# nes-forever.net
KiCad netlist of a schematic drawn in EAGLE
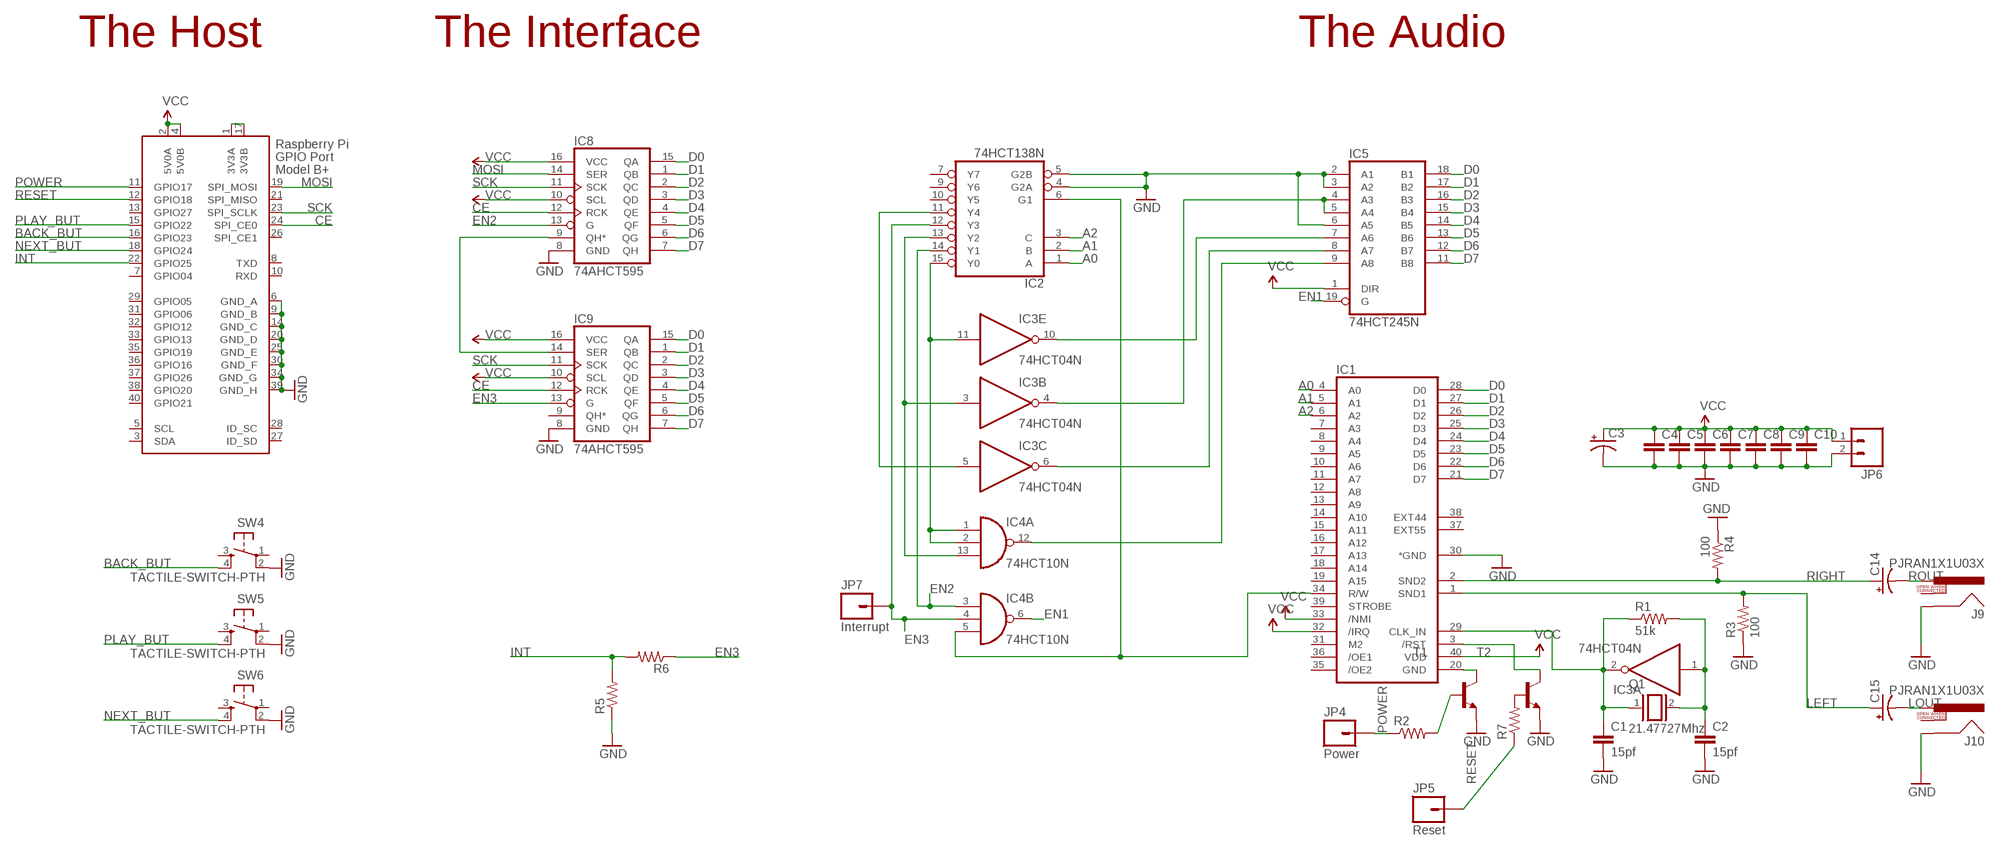
[diagram p0: schematic, sheet 1]

(export (version "E")
  (design (tool "Eeschema 10.0.6"))
  (components
    (comp (ref "C1")
      (value "15pf")
      (footprint "eagle-import:C025-024X044")
      (libsource (lib "eagle-import") (part "C-EU025-024X044"))
    )
    (comp (ref "C2")
      (value "15pf")
      (footprint "eagle-import:C025-024X044")
      (libsource (lib "eagle-import") (part "C-EU025-024X044"))
    )
    (comp (ref "C3")
      (value "CPOL-USE5-8.5")
      (footprint "eagle-import:E5-8,5")
      (libsource (lib "eagle-import") (part "CPOL-USE5-8.5"))
    )
    (comp (ref "C4")
      (value "C-EU025-024X044")
      (footprint "eagle-import:C025-024X044")
      (libsource (lib "eagle-import") (part "C-EU025-024X044"))
    )
    (comp (ref "C5")
      (value "C-EU025-024X044")
      (footprint "eagle-import:C025-024X044")
      (libsource (lib "eagle-import") (part "C-EU025-024X044"))
    )
    (comp (ref "C6")
      (value "C-EU025-024X044")
      (footprint "eagle-import:C025-024X044")
      (libsource (lib "eagle-import") (part "C-EU025-024X044"))
    )
    (comp (ref "C7")
      (value "C-EU025-024X044")
      (footprint "eagle-import:C025-024X044")
      (libsource (lib "eagle-import") (part "C-EU025-024X044"))
    )
    (comp (ref "C8")
      (value "C-EU025-024X044")
      (footprint "eagle-import:C025-024X044")
      (libsource (lib "eagle-import") (part "C-EU025-024X044"))
    )
    (comp (ref "C9")
      (value "C-EU025-024X044")
      (footprint "eagle-import:C025-024X044")
      (libsource (lib "eagle-import") (part "C-EU025-024X044"))
    )
    (comp (ref "C10")
      (value "C-EU025-024X044")
      (footprint "eagle-import:C025-024X044")
      (libsource (lib "eagle-import") (part "C-EU025-024X044"))
    )
    (comp (ref "C14")
      (value "CPOL-USE2-4")
      (footprint "eagle-import:E2-4")
      (libsource (lib "eagle-import") (part "resistor_CPOL-USE2-4"))
    )
    (comp (ref "C15")
      (value "CPOL-USE2-4")
      (footprint "eagle-import:E2-4")
      (libsource (lib "eagle-import") (part "resistor_CPOL-USE2-4"))
    )
    (comp (ref "IC1")
      (value "2A03")
      (footprint "eagle-import:DIL40")
      (libsource (lib "eagle-import") (part "2A03"))
    )
    (comp (ref "IC2")
      (value "74HCT138N")
      (footprint "eagle-import:DIL16")
      (libsource (lib "eagle-import") (part "74138NHCT"))
    )
    (comp (ref "IC3")
      (value "74HCT04N")
      (footprint "eagle-import:DIL14")
      (libsource (lib "eagle-import") (part "7404NHCT"))
    )
    (comp (ref "IC4")
      (value "74HCT10N")
      (footprint "eagle-import:DIL14")
      (libsource (lib "eagle-import") (part "7410NHCT"))
    )
    (comp (ref "IC5")
      (value "74HCT245N")
      (footprint "eagle-import:DIL20")
      (libsource (lib "eagle-import") (part "74245NHCT"))
    )
    (comp (ref "IC8")
      (value "74AHCT595")
      (footprint "eagle-import:DIL16")
      (libsource (lib "eagle-import") (part "74595NLS"))
    )
    (comp (ref "IC9")
      (value "74AHCT595")
      (footprint "eagle-import:DIL16")
      (libsource (lib "eagle-import") (part "74595NLS"))
    )
    (comp (ref "J9")
      (value "PJRAN1X1U03X")
      (footprint "eagle-import:RCA")
      (libsource (lib "eagle-import") (part "RCA"))
    )
    (comp (ref "J10")
      (value "PJRAN1X1U03X")
      (footprint "eagle-import:RCA")
      (libsource (lib "eagle-import") (part "RCA"))
    )
    (comp (ref "JP4")
      (value "Power")
      (footprint "eagle-import:1X01")
      (libsource (lib "eagle-import") (part "M01PTH"))
    )
    (comp (ref "JP5")
      (value "Reset")
      (footprint "eagle-import:1X01")
      (libsource (lib "eagle-import") (part "M01PTH"))
    )
    (comp (ref "JP6")
      (value "M02")
      (footprint "eagle-import:1X02_LONGPADS")
      (libsource (lib "eagle-import") (part "M02"))
    )
    (comp (ref "JP7")
      (value "Interrupt")
      (footprint "eagle-import:1X01")
      (libsource (lib "eagle-import") (part "M01PTH"))
    )
    (comp (ref "Q1")
      (value "21.47727Mhz")
      (footprint "eagle-import:Q")
      (libsource (lib "eagle-import") (part "XTAL"))
    )
    (comp (ref "R1")
      (value "51k")
      (footprint "eagle-import:0207_7")
      (libsource (lib "eagle-import") (part "R-US_0207/7"))
    )
    (comp (ref "R2")
      (value "R-US_0207/7")
      (footprint "eagle-import:0207_7")
      (libsource (lib "eagle-import") (part "R-US_0207/7"))
    )
    (comp (ref "R3")
      (value "100")
      (footprint "eagle-import:0207_7")
      (libsource (lib "eagle-import") (part "R-US_0207/7"))
    )
    (comp (ref "R4")
      (value "100")
      (footprint "eagle-import:0207_7")
      (libsource (lib "eagle-import") (part "R-US_0207/7"))
    )
    (comp (ref "R5")
      (value "R-US_0207/7")
      (footprint "eagle-import:0207_7")
      (libsource (lib "eagle-import") (part "R-US_0207/7"))
    )
    (comp (ref "R6")
      (value "R-US_0207/7")
      (footprint "eagle-import:0207_7")
      (libsource (lib "eagle-import") (part "R-US_0207/7"))
    )
    (comp (ref "R7")
      (value "R-US_0207/7")
      (footprint "eagle-import:0207_7")
      (libsource (lib "eagle-import") (part "R-US_0207/7"))
    )
    (comp (ref "SW4")
      (value "TACTILE-SWITCH-PTH")
      (footprint "eagle-import:TAC-SWITCH-PTH")
      (libsource (lib "eagle-import") (part "TACTILE-SWITCH-PTH"))
    )
    (comp (ref "SW5")
      (value "TACTILE-SWITCH-PTH")
      (footprint "eagle-import:TAC-SWITCH-PTH")
      (libsource (lib "eagle-import") (part "TACTILE-SWITCH-PTH"))
    )
    (comp (ref "SW6")
      (value "TACTILE-SWITCH-PTH")
      (footprint "eagle-import:TAC-SWITCH-PTH")
      (libsource (lib "eagle-import") (part "TACTILE-SWITCH-PTH"))
    )
    (comp (ref "T1")
      (value "2N2222-NPN-TO92-EBC")
      (footprint "eagle-import:TO92-EBC")
      (libsource (lib "eagle-import") (part "-NPN-TO92-EBC2N2222"))
    )
    (comp (ref "T2")
      (value "2N2222-NPN-TO92-EBC")
      (footprint "eagle-import:TO92-EBC")
      (libsource (lib "eagle-import") (part "-NPN-TO92-EBC2N2222"))
    )
    (comp (ref "X2")
      (value "RASPI_BOARD_B+#_E4")
      (footprint "eagle-import:RASPI_BOARD_B+_EDGES_4DRILL")
      (libsource (lib "eagle-import") (part "RASPI_BOARD_B+#_E4"))
    )
  )
  (nets
    (net (code "1") (name "/A0") (class "Default")
      (node (ref "IC1") (pin "4") (pinfunction "A0_4") (pintype "output"))
      (node (ref "IC2") (pin "1") (pinfunction "A_1") (pintype "input"))
    )
    (net (code "2") (name "/A1") (class "Default")
      (node (ref "IC1") (pin "5") (pinfunction "A1_5") (pintype "output"))
      (node (ref "IC2") (pin "2") (pinfunction "B_2") (pintype "input"))
    )
    (net (code "3") (name "/A2") (class "Default")
      (node (ref "IC1") (pin "6") (pinfunction "A2_6") (pintype "output"))
      (node (ref "IC2") (pin "3") (pinfunction "C_3") (pintype "input"))
    )
    (net (code "4") (name "/BACK_BUT") (class "Default")
      (node (ref "SW4") (pin "4") (pinfunction "4_4") (pintype "passive"))
      (node (ref "X2") (pin "16") (pinfunction "GPIO23_16") (pintype "bidirectional"))
    )
    (net (code "5") (name "/CE") (class "Default")
      (node (ref "IC8") (pin "12") (pinfunction "RCK_12") (pintype "input"))
      (node (ref "IC9") (pin "12") (pinfunction "RCK_12") (pintype "input"))
      (node (ref "X2") (pin "24") (pinfunction "SPI_CE0_24") (pintype "bidirectional"))
    )
    (net (code "6") (name "/D0") (class "Default")
      (node (ref "IC1") (pin "28") (pinfunction "D0_28") (pintype "bidirectional"))
      (node (ref "IC5") (pin "18") (pinfunction "B1_18") (pintype "bidirectional"))
      (node (ref "IC8") (pin "15") (pinfunction "QA_15") (pintype "tri_state"))
      (node (ref "IC9") (pin "15") (pinfunction "QA_15") (pintype "tri_state"))
    )
    (net (code "7") (name "/D1") (class "Default")
      (node (ref "IC1") (pin "27") (pinfunction "D1_27") (pintype "bidirectional"))
      (node (ref "IC5") (pin "17") (pinfunction "B2_17") (pintype "bidirectional"))
      (node (ref "IC8") (pin "1") (pinfunction "QB_1") (pintype "tri_state"))
      (node (ref "IC9") (pin "1") (pinfunction "QB_1") (pintype "tri_state"))
    )
    (net (code "8") (name "/D2") (class "Default")
      (node (ref "IC1") (pin "26") (pinfunction "D2_26") (pintype "bidirectional"))
      (node (ref "IC5") (pin "16") (pinfunction "B3_16") (pintype "bidirectional"))
      (node (ref "IC8") (pin "2") (pinfunction "QC_2") (pintype "tri_state"))
      (node (ref "IC9") (pin "2") (pinfunction "QC_2") (pintype "tri_state"))
    )
    (net (code "9") (name "/D3") (class "Default")
      (node (ref "IC1") (pin "25") (pinfunction "D3_25") (pintype "bidirectional"))
      (node (ref "IC5") (pin "15") (pinfunction "B4_15") (pintype "bidirectional"))
      (node (ref "IC8") (pin "3") (pinfunction "QD_3") (pintype "tri_state"))
      (node (ref "IC9") (pin "3") (pinfunction "QD_3") (pintype "tri_state"))
    )
    (net (code "10") (name "/D4") (class "Default")
      (node (ref "IC1") (pin "24") (pinfunction "D4_24") (pintype "bidirectional"))
      (node (ref "IC5") (pin "14") (pinfunction "B5_14") (pintype "bidirectional"))
      (node (ref "IC8") (pin "4") (pinfunction "QE_4") (pintype "tri_state"))
      (node (ref "IC9") (pin "4") (pinfunction "QE_4") (pintype "tri_state"))
    )
    (net (code "11") (name "/D5") (class "Default")
      (node (ref "IC1") (pin "23") (pinfunction "D5_23") (pintype "bidirectional"))
      (node (ref "IC5") (pin "13") (pinfunction "B6_13") (pintype "bidirectional"))
      (node (ref "IC8") (pin "5") (pinfunction "QF_5") (pintype "tri_state"))
      (node (ref "IC9") (pin "5") (pinfunction "QF_5") (pintype "tri_state"))
    )
    (net (code "12") (name "/D6") (class "Default")
      (node (ref "IC1") (pin "22") (pinfunction "D6_22") (pintype "bidirectional"))
      (node (ref "IC5") (pin "12") (pinfunction "B7_12") (pintype "bidirectional"))
      (node (ref "IC8") (pin "6") (pinfunction "QG_6") (pintype "tri_state"))
      (node (ref "IC9") (pin "6") (pinfunction "QG_6") (pintype "tri_state"))
    )
    (net (code "13") (name "/D7") (class "Default")
      (node (ref "IC1") (pin "21") (pinfunction "D7_21") (pintype "bidirectional"))
      (node (ref "IC5") (pin "11") (pinfunction "B8_11") (pintype "bidirectional"))
      (node (ref "IC8") (pin "7") (pinfunction "QH_7") (pintype "tri_state"))
      (node (ref "IC9") (pin "7") (pinfunction "QH_7") (pintype "tri_state"))
    )
    (net (code "14") (name "/EN1") (class "Default")
      (node (ref "IC4") (pin "6") (pinfunction "O_6") (pintype "output"))
      (node (ref "IC5") (pin "19") (pinfunction "G_19") (pintype "input"))
    )
    (net (code "15") (name "/EN2") (class "Default")
      (node (ref "IC2") (pin "14") (pinfunction "Y1_14") (pintype "output"))
      (node (ref "IC4") (pin "3") (pinfunction "I0_3") (pintype "input"))
      (node (ref "IC8") (pin "13") (pinfunction "G_13") (pintype "input"))
    )
    (net (code "16") (name "/EN3") (class "Default")
      (node (ref "IC2") (pin "12") (pinfunction "Y3_12") (pintype "output"))
      (node (ref "IC4") (pin "4") (pinfunction "I1_4") (pintype "input"))
      (node (ref "IC9") (pin "13") (pinfunction "G_13") (pintype "input"))
      (node (ref "JP7") (pin "1") (pinfunction "1_1") (pintype "passive"))
      (node (ref "R6") (pin "1") (pinfunction "1_1") (pintype "passive"))
    )
    (net (code "17") (name "/INT") (class "Default")
      (node (ref "R5") (pin "2") (pinfunction "2_2") (pintype "passive"))
      (node (ref "R6") (pin "2") (pinfunction "2_2") (pintype "passive"))
      (node (ref "X2") (pin "22") (pinfunction "GPIO25_22") (pintype "bidirectional"))
    )
    (net (code "18") (name "/LEFT") (class "Default")
      (node (ref "C15") (pin "+") (pinfunction "+_+") (pintype "passive"))
      (node (ref "IC1") (pin "1") (pinfunction "SND1_1") (pintype "output"))
      (node (ref "R3") (pin "2") (pinfunction "2_2") (pintype "passive"))
    )
    (net (code "19") (name "/LOUT") (class "Default")
      (node (ref "C15") (pin "-") (pinfunction "-_-") (pintype "passive"))
      (node (ref "J10") (pin "PIN") (pinfunction "PIN_PIN") (pintype "bidirectional"))
    )
    (net (code "20") (name "/MOSI") (class "Default")
      (node (ref "IC8") (pin "14") (pinfunction "SER_14") (pintype "input"))
      (node (ref "X2") (pin "19") (pinfunction "SPI_MOSI_19") (pintype "bidirectional"))
    )
    (net (code "21") (name "/NEXT_BUT") (class "Default")
      (node (ref "SW6") (pin "4") (pinfunction "4_4") (pintype "passive"))
      (node (ref "X2") (pin "18") (pinfunction "GPIO24_18") (pintype "bidirectional"))
    )
    (net (code "22") (name "/PLAY_BUT") (class "Default")
      (node (ref "SW5") (pin "4") (pinfunction "4_4") (pintype "passive"))
      (node (ref "X2") (pin "15") (pinfunction "GPIO22_15") (pintype "bidirectional"))
    )
    (net (code "23") (name "/POWER") (class "Default")
      (node (ref "JP4") (pin "1") (pinfunction "1_1") (pintype "passive"))
      (node (ref "R2") (pin "1") (pinfunction "1_1") (pintype "passive"))
      (node (ref "X2") (pin "11") (pinfunction "GPIO17_11") (pintype "bidirectional"))
    )
    (net (code "24") (name "/RESET") (class "Default")
      (node (ref "JP5") (pin "1") (pinfunction "1_1") (pintype "passive"))
      (node (ref "R7") (pin "1") (pinfunction "1_1") (pintype "passive"))
      (node (ref "X2") (pin "12") (pinfunction "GPIO18_12") (pintype "bidirectional"))
    )
    (net (code "25") (name "/RIGHT") (class "Default")
      (node (ref "C14") (pin "+") (pinfunction "+_+") (pintype "passive"))
      (node (ref "IC1") (pin "2") (pinfunction "SND2_2") (pintype "output"))
      (node (ref "R4") (pin "2") (pinfunction "2_2") (pintype "passive"))
    )
    (net (code "26") (name "/ROUT") (class "Default")
      (node (ref "C14") (pin "-") (pinfunction "-_-") (pintype "passive"))
      (node (ref "J9") (pin "PIN") (pinfunction "PIN_PIN") (pintype "bidirectional"))
    )
    (net (code "27") (name "/SCK") (class "Default")
      (node (ref "IC8") (pin "11") (pinfunction "SCK_11") (pintype "input"))
      (node (ref "IC9") (pin "11") (pinfunction "SCK_11") (pintype "input"))
      (node (ref "X2") (pin "23") (pinfunction "SPI_SCLK_23") (pintype "bidirectional"))
    )
    (net (code "28") (name "GND") (class "Default")
      (node (ref "C1") (pin "2") (pinfunction "2_2") (pintype "passive"))
      (node (ref "C10") (pin "2") (pinfunction "2_2") (pintype "passive"))
      (node (ref "C2") (pin "2") (pinfunction "2_2") (pintype "passive"))
      (node (ref "C3") (pin "-") (pinfunction "-_-") (pintype "passive"))
      (node (ref "C4") (pin "2") (pinfunction "2_2") (pintype "passive"))
      (node (ref "C5") (pin "2") (pinfunction "2_2") (pintype "passive"))
      (node (ref "C6") (pin "2") (pinfunction "2_2") (pintype "passive"))
      (node (ref "C7") (pin "2") (pinfunction "2_2") (pintype "passive"))
      (node (ref "C8") (pin "2") (pinfunction "2_2") (pintype "passive"))
      (node (ref "C9") (pin "2") (pinfunction "2_2") (pintype "passive"))
      (node (ref "IC1") (pin "30") (pinfunction "*GND_30") (pintype "output"))
      (node (ref "IC2") (pin "4") (pinfunction "G2A_4") (pintype "input"))
      (node (ref "IC2") (pin "5") (pinfunction "G2B_5") (pintype "input"))
      (node (ref "IC5") (pin "2") (pinfunction "A1_2") (pintype "bidirectional"))
      (node (ref "IC5") (pin "3") (pinfunction "A2_3") (pintype "bidirectional"))
      (node (ref "IC5") (pin "6") (pinfunction "A5_6") (pintype "bidirectional"))
      (node (ref "IC8") (pin "8") (pinfunction "GND_8") (pintype "power_in"))
      (node (ref "IC9") (pin "8") (pinfunction "GND_8") (pintype "power_in"))
      (node (ref "J10") (pin "SHELL") (pinfunction "SHELL_SHELL") (pintype "bidirectional"))
      (node (ref "J9") (pin "SHELL") (pinfunction "SHELL_SHELL") (pintype "bidirectional"))
      (node (ref "JP6") (pin "2") (pinfunction "2_2") (pintype "passive"))
      (node (ref "R3") (pin "1") (pinfunction "1_1") (pintype "passive"))
      (node (ref "R4") (pin "1") (pinfunction "1_1") (pintype "passive"))
      (node (ref "R5") (pin "1") (pinfunction "1_1") (pintype "passive"))
      (node (ref "SW4") (pin "2") (pinfunction "2_2") (pintype "passive"))
      (node (ref "SW5") (pin "2") (pinfunction "2_2") (pintype "passive"))
      (node (ref "SW6") (pin "2") (pinfunction "2_2") (pintype "passive"))
      (node (ref "T1") (pin "E") (pinfunction "E_E") (pintype "passive"))
      (node (ref "T2") (pin "E") (pinfunction "E_E") (pintype "passive"))
      (node (ref "X2") (pin "14") (pinfunction "GND_C_14") (pintype "power_in"))
      (node (ref "X2") (pin "20") (pinfunction "GND_D_20") (pintype "power_in"))
      (node (ref "X2") (pin "25") (pinfunction "GND_E_25") (pintype "power_in"))
      (node (ref "X2") (pin "30") (pinfunction "GND_F_30") (pintype "power_in"))
      (node (ref "X2") (pin "34") (pinfunction "GND_G_34") (pintype "power_in"))
      (node (ref "X2") (pin "39") (pinfunction "GND_H_39") (pintype "power_in"))
      (node (ref "X2") (pin "6") (pinfunction "GND_A_6") (pintype "power_in"))
      (node (ref "X2") (pin "9") (pinfunction "GND_B_9") (pintype "power_in"))
    )
    (net (code "29") (name "Net-(IC1-CLK_IN)") (class "Default")
      (node (ref "C1") (pin "1") (pinfunction "1_1") (pintype "passive"))
      (node (ref "IC1") (pin "29") (pinfunction "CLK_IN_29") (pintype "input"))
      (node (ref "IC3") (pin "2") (pinfunction "O_2") (pintype "output"))
      (node (ref "Q1") (pin "1") (pinfunction "1_1") (pintype "passive"))
      (node (ref "R1") (pin "1") (pinfunction "1_1") (pintype "passive"))
    )
    (net (code "30") (name "Net-(IC1-GND)") (class "Default")
      (node (ref "IC1") (pin "20") (pinfunction "GND_20") (pintype "power_in"))
      (node (ref "T1") (pin "C") (pinfunction "C_C") (pintype "passive"))
    )
    (net (code "31") (name "Net-(IC1-R{slash}W)") (class "Default")
      (node (ref "IC1") (pin "34") (pinfunction "R/W_34") (pintype "input"))
      (node (ref "IC2") (pin "6") (pinfunction "G1_6") (pintype "input"))
      (node (ref "IC4") (pin "5") (pinfunction "I2_5") (pintype "input"))
    )
    (net (code "32") (name "Net-(IC1-{slash}RST)") (class "Default")
      (node (ref "IC1") (pin "3") (pinfunction "/RST_3") (pintype "output"))
      (node (ref "T2") (pin "C") (pinfunction "C_C") (pintype "passive"))
    )
    (net (code "33") (name "Net-(IC2A-Y0)") (class "Default")
      (node (ref "IC2") (pin "15") (pinfunction "Y0_15") (pintype "output"))
      (node (ref "IC3") (pin "11") (pinfunction "I_11") (pintype "input"))
      (node (ref "IC4") (pin "1") (pinfunction "I0_1") (pintype "input"))
      (node (ref "IC4") (pin "2") (pinfunction "I1_2") (pintype "input"))
    )
    (net (code "34") (name "Net-(IC2A-Y2)") (class "Default")
      (node (ref "IC2") (pin "13") (pinfunction "Y2_13") (pintype "output"))
      (node (ref "IC3") (pin "3") (pinfunction "I_3") (pintype "input"))
      (node (ref "IC4") (pin "13") (pinfunction "I2_13") (pintype "input"))
    )
    (net (code "35") (name "Net-(IC2A-Y4)") (class "Default")
      (node (ref "IC2") (pin "11") (pinfunction "Y4_11") (pintype "output"))
      (node (ref "IC3") (pin "5") (pinfunction "I_5") (pintype "input"))
    )
    (net (code "36") (name "Net-(IC3A-I)") (class "Default")
      (node (ref "C2") (pin "1") (pinfunction "1_1") (pintype "passive"))
      (node (ref "IC3") (pin "1") (pinfunction "I_1") (pintype "input"))
      (node (ref "Q1") (pin "2") (pinfunction "2_2") (pintype "passive"))
      (node (ref "R1") (pin "2") (pinfunction "2_2") (pintype "passive"))
    )
    (net (code "37") (name "Net-(IC3B-O)") (class "Default")
      (node (ref "IC3") (pin "4") (pinfunction "O_4") (pintype "output"))
      (node (ref "IC5") (pin "4") (pinfunction "A3_4") (pintype "bidirectional"))
      (node (ref "IC5") (pin "5") (pinfunction "A4_5") (pintype "bidirectional"))
    )
    (net (code "38") (name "Net-(IC3C-O)") (class "Default")
      (node (ref "IC3") (pin "6") (pinfunction "O_6") (pintype "output"))
      (node (ref "IC5") (pin "8") (pinfunction "A7_8") (pintype "bidirectional"))
    )
    (net (code "39") (name "Net-(IC3E-O)") (class "Default")
      (node (ref "IC3") (pin "10") (pinfunction "O_10") (pintype "output"))
      (node (ref "IC5") (pin "7") (pinfunction "A6_7") (pintype "bidirectional"))
    )
    (net (code "40") (name "Net-(IC4A-O)") (class "Default")
      (node (ref "IC4") (pin "12") (pinfunction "O_12") (pintype "output"))
      (node (ref "IC5") (pin "9") (pinfunction "A8_9") (pintype "bidirectional"))
    )
    (net (code "41") (name "Net-(IC8-QH*)") (class "Default")
      (node (ref "IC8") (pin "9") (pinfunction "QH*_9") (pintype "tri_state"))
      (node (ref "IC9") (pin "14") (pinfunction "SER_14") (pintype "input"))
    )
    (net (code "42") (name "Net-(R2-Pad2)") (class "Default")
      (node (ref "R2") (pin "2") (pinfunction "2_2") (pintype "passive"))
      (node (ref "T1") (pin "B") (pinfunction "B_B") (pintype "passive"))
    )
    (net (code "43") (name "Net-(R7-Pad2)") (class "Default")
      (node (ref "R7") (pin "2") (pinfunction "2_2") (pintype "passive"))
      (node (ref "T2") (pin "B") (pinfunction "B_B") (pintype "passive"))
    )
    (net (code "44") (name "Net-(X2-3V3A)") (class "Default")
      (node (ref "X2") (pin "1") (pinfunction "3V3A_1") (pintype "power_in"))
      (node (ref "X2") (pin "17") (pinfunction "3V3B_17") (pintype "power_in"))
    )
    (net (code "45") (name "VCC") (class "Default")
      (node (ref "C10") (pin "1") (pinfunction "1_1") (pintype "passive"))
      (node (ref "C3") (pin "+") (pinfunction "+_+") (pintype "passive"))
      (node (ref "C4") (pin "1") (pinfunction "1_1") (pintype "passive"))
      (node (ref "C5") (pin "1") (pinfunction "1_1") (pintype "passive"))
      (node (ref "C6") (pin "1") (pinfunction "1_1") (pintype "passive"))
      (node (ref "C7") (pin "1") (pinfunction "1_1") (pintype "passive"))
      (node (ref "C8") (pin "1") (pinfunction "1_1") (pintype "passive"))
      (node (ref "C9") (pin "1") (pinfunction "1_1") (pintype "passive"))
      (node (ref "IC1") (pin "32") (pinfunction "/IRQ_32") (pintype "input"))
      (node (ref "IC1") (pin "33") (pinfunction "/NMI_33") (pintype "input"))
      (node (ref "IC1") (pin "40") (pinfunction "VDD_40") (pintype "power_in"))
      (node (ref "IC5") (pin "1") (pinfunction "DIR_1") (pintype "input"))
      (node (ref "IC8") (pin "10") (pinfunction "SCL_10") (pintype "input"))
      (node (ref "IC8") (pin "16") (pinfunction "VCC_16") (pintype "power_in"))
      (node (ref "IC9") (pin "10") (pinfunction "SCL_10") (pintype "input"))
      (node (ref "IC9") (pin "16") (pinfunction "VCC_16") (pintype "power_in"))
      (node (ref "JP6") (pin "1") (pinfunction "1_1") (pintype "passive"))
      (node (ref "X2") (pin "2") (pinfunction "5V0A_2") (pintype "power_in"))
      (node (ref "X2") (pin "4") (pinfunction "5V0B_4") (pintype "power_in"))
    )
    (net (code "46") (name "unconnected-(IC1-A3-Pad7)") (class "Default")
      (node (ref "IC1") (pin "7") (pinfunction "A3_7") (pintype "output"))
    )
    (net (code "47") (name "unconnected-(IC1-A4-Pad8)") (class "Default")
      (node (ref "IC1") (pin "8") (pinfunction "A4_8") (pintype "output"))
    )
    (net (code "48") (name "unconnected-(IC1-A5-Pad9)") (class "Default")
      (node (ref "IC1") (pin "9") (pinfunction "A5_9") (pintype "output"))
    )
    (net (code "49") (name "unconnected-(IC1-A6-Pad10)") (class "Default")
      (node (ref "IC1") (pin "10") (pinfunction "A6_10") (pintype "output"))
    )
    (net (code "50") (name "unconnected-(IC1-A7-Pad11)") (class "Default")
      (node (ref "IC1") (pin "11") (pinfunction "A7_11") (pintype "output"))
    )
    (net (code "51") (name "unconnected-(IC1-A8-Pad12)") (class "Default")
      (node (ref "IC1") (pin "12") (pinfunction "A8_12") (pintype "output"))
    )
    (net (code "52") (name "unconnected-(IC1-A9-Pad13)") (class "Default")
      (node (ref "IC1") (pin "13") (pinfunction "A9_13") (pintype "output"))
    )
    (net (code "53") (name "unconnected-(IC1-A10-Pad14)") (class "Default")
      (node (ref "IC1") (pin "14") (pinfunction "A10_14") (pintype "output"))
    )
    (net (code "54") (name "unconnected-(IC1-A11-Pad15)") (class "Default")
      (node (ref "IC1") (pin "15") (pinfunction "A11_15") (pintype "output"))
    )
    (net (code "55") (name "unconnected-(IC1-A12-Pad16)") (class "Default")
      (node (ref "IC1") (pin "16") (pinfunction "A12_16") (pintype "bidirectional"))
    )
    (net (code "56") (name "unconnected-(IC1-A13-Pad17)") (class "Default")
      (node (ref "IC1") (pin "17") (pinfunction "A13_17") (pintype "bidirectional"))
    )
    (net (code "57") (name "unconnected-(IC1-A14-Pad18)") (class "Default")
      (node (ref "IC1") (pin "18") (pinfunction "A14_18") (pintype "bidirectional"))
    )
    (net (code "58") (name "unconnected-(IC1-A15-Pad19)") (class "Default")
      (node (ref "IC1") (pin "19") (pinfunction "A15_19") (pintype "bidirectional"))
    )
    (net (code "59") (name "unconnected-(IC1-EXT44-Pad38)") (class "Default")
      (node (ref "IC1") (pin "38") (pinfunction "EXT44_38") (pintype "bidirectional"))
    )
    (net (code "60") (name "unconnected-(IC1-EXT55-Pad37)") (class "Default")
      (node (ref "IC1") (pin "37") (pinfunction "EXT55_37") (pintype "bidirectional"))
    )
    (net (code "61") (name "unconnected-(IC1-M2-Pad31)") (class "Default")
      (node (ref "IC1") (pin "31") (pinfunction "M2_31") (pintype "input"))
    )
    (net (code "62") (name "unconnected-(IC1-STROBE-Pad39)") (class "Default")
      (node (ref "IC1") (pin "39") (pinfunction "STROBE_39") (pintype "bidirectional"))
    )
    (net (code "63") (name "unconnected-(IC1-{slash}OE1-Pad36)") (class "Default")
      (node (ref "IC1") (pin "36") (pinfunction "/OE1_36") (pintype "bidirectional"))
    )
    (net (code "64") (name "unconnected-(IC1-{slash}OE2-Pad35)") (class "Default")
      (node (ref "IC1") (pin "35") (pinfunction "/OE2_35") (pintype "input"))
    )
    (net (code "65") (name "unconnected-(IC2A-Y5-Pad10)") (class "Default")
      (node (ref "IC2") (pin "10") (pinfunction "Y5_10") (pintype "output"))
    )
    (net (code "66") (name "unconnected-(IC2A-Y6-Pad9)") (class "Default")
      (node (ref "IC2") (pin "9") (pinfunction "Y6_9") (pintype "output"))
    )
    (net (code "67") (name "unconnected-(IC2A-Y7-Pad7)") (class "Default")
      (node (ref "IC2") (pin "7") (pinfunction "Y7_7") (pintype "output"))
    )
    (net (code "68") (name "unconnected-(IC9-QH*-Pad9)") (class "Default")
      (node (ref "IC9") (pin "9") (pinfunction "QH*_9") (pintype "tri_state"))
    )
    (net (code "69") (name "unconnected-(J9-PadSWITCH)") (class "Default")
      (node (ref "J9") (pin "SWITCH") (pinfunction "SWITCH_SWITCH") (pintype "bidirectional"))
    )
    (net (code "70") (name "unconnected-(J10-PadSWITCH)") (class "Default")
      (node (ref "J10") (pin "SWITCH") (pinfunction "SWITCH_SWITCH") (pintype "bidirectional"))
    )
    (net (code "71") (name "unconnected-(SW4-Pad1)") (class "Default")
      (node (ref "SW4") (pin "1") (pinfunction "1_1") (pintype "passive"))
    )
    (net (code "72") (name "unconnected-(SW4-Pad3)") (class "Default")
      (node (ref "SW4") (pin "3") (pinfunction "3_3") (pintype "passive"))
    )
    (net (code "73") (name "unconnected-(SW5-Pad1)") (class "Default")
      (node (ref "SW5") (pin "1") (pinfunction "1_1") (pintype "passive"))
    )
    (net (code "74") (name "unconnected-(SW5-Pad3)") (class "Default")
      (node (ref "SW5") (pin "3") (pinfunction "3_3") (pintype "passive"))
    )
    (net (code "75") (name "unconnected-(SW6-Pad1)") (class "Default")
      (node (ref "SW6") (pin "1") (pinfunction "1_1") (pintype "passive"))
    )
    (net (code "76") (name "unconnected-(SW6-Pad3)") (class "Default")
      (node (ref "SW6") (pin "3") (pinfunction "3_3") (pintype "passive"))
    )
    (net (code "77") (name "unconnected-(X2-GPIO04-Pad7)") (class "Default")
      (node (ref "X2") (pin "7") (pinfunction "GPIO04_7") (pintype "bidirectional"))
    )
    (net (code "78") (name "unconnected-(X2-GPIO05-Pad29)") (class "Default")
      (node (ref "X2") (pin "29") (pinfunction "GPIO05_29") (pintype "no_connect"))
    )
    (net (code "79") (name "unconnected-(X2-GPIO06-Pad31)") (class "Default")
      (node (ref "X2") (pin "31") (pinfunction "GPIO06_31") (pintype "no_connect"))
    )
    (net (code "80") (name "unconnected-(X2-GPIO12-Pad32)") (class "Default")
      (node (ref "X2") (pin "32") (pinfunction "GPIO12_32") (pintype "no_connect"))
    )
    (net (code "81") (name "unconnected-(X2-GPIO13-Pad33)") (class "Default")
      (node (ref "X2") (pin "33") (pinfunction "GPIO13_33") (pintype "no_connect"))
    )
    (net (code "82") (name "unconnected-(X2-GPIO16-Pad36)") (class "Default")
      (node (ref "X2") (pin "36") (pinfunction "GPIO16_36") (pintype "no_connect"))
    )
    (net (code "83") (name "unconnected-(X2-GPIO19-Pad35)") (class "Default")
      (node (ref "X2") (pin "35") (pinfunction "GPIO19_35") (pintype "no_connect"))
    )
    (net (code "84") (name "unconnected-(X2-GPIO20-Pad38)") (class "Default")
      (node (ref "X2") (pin "38") (pinfunction "GPIO20_38") (pintype "no_connect"))
    )
    (net (code "85") (name "unconnected-(X2-GPIO21-Pad40)") (class "Default")
      (node (ref "X2") (pin "40") (pinfunction "GPIO21_40") (pintype "no_connect"))
    )
    (net (code "86") (name "unconnected-(X2-GPIO26-Pad37)") (class "Default")
      (node (ref "X2") (pin "37") (pinfunction "GPIO26_37") (pintype "no_connect"))
    )
    (net (code "87") (name "unconnected-(X2-GPIO27-Pad13)") (class "Default")
      (node (ref "X2") (pin "13") (pinfunction "GPIO27_13") (pintype "bidirectional"))
    )
    (net (code "88") (name "unconnected-(X2-ID_SC-Pad28)") (class "Default")
      (node (ref "X2") (pin "28") (pinfunction "ID_SC_28") (pintype "no_connect"))
    )
    (net (code "89") (name "unconnected-(X2-ID_SD-Pad27)") (class "Default")
      (node (ref "X2") (pin "27") (pinfunction "ID_SD_27") (pintype "no_connect"))
    )
    (net (code "90") (name "unconnected-(X2-RXD-Pad10)") (class "Default")
      (node (ref "X2") (pin "10") (pinfunction "RXD_10") (pintype "bidirectional"))
    )
    (net (code "91") (name "unconnected-(X2-SCL-Pad5)") (class "Default")
      (node (ref "X2") (pin "5") (pinfunction "SCL_5") (pintype "bidirectional"))
    )
    (net (code "92") (name "unconnected-(X2-SDA-Pad3)") (class "Default")
      (node (ref "X2") (pin "3") (pinfunction "SDA_3") (pintype "bidirectional"))
    )
    (net (code "93") (name "unconnected-(X2-SPI_CE1-Pad26)") (class "Default")
      (node (ref "X2") (pin "26") (pinfunction "SPI_CE1_26") (pintype "bidirectional"))
    )
    (net (code "94") (name "unconnected-(X2-SPI_MISO-Pad21)") (class "Default")
      (node (ref "X2") (pin "21") (pinfunction "SPI_MISO_21") (pintype "bidirectional"))
    )
    (net (code "95") (name "unconnected-(X2-TXD-Pad8)") (class "Default")
      (node (ref "X2") (pin "8") (pinfunction "TXD_8") (pintype "bidirectional"))
    )
  )
)
